# output_filter_LC.net
KiCad netlist of a schematic drawn in Altium Designer
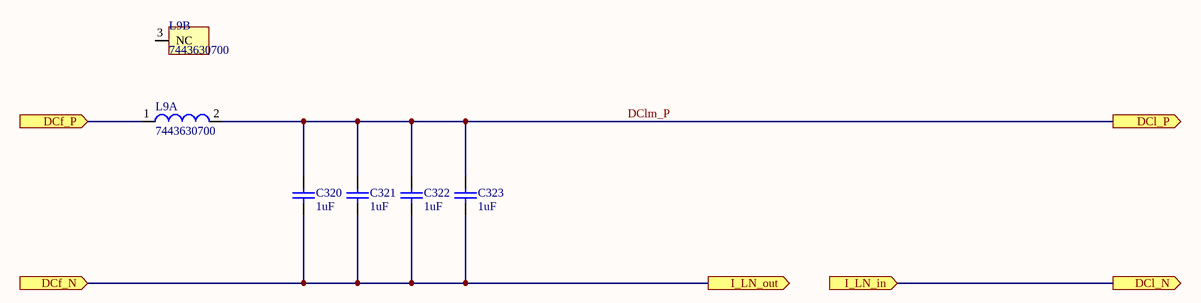
[diagram p0: output_filter_LC.SchDoc]

(export (version "E")
  (design (tool "Eeschema 10.0.6"))
  (components
    (comp (ref "C320")
      (value "1uF")
      (footprint "CAPC2225(5664)230_L")
      (description "CAP 1uF 200V ±10% 2225 (5664 Metric) Thickness 2.2mm SMD")
      (fields (field (name "TOLERANCE") "Â±10%") (field (name "Comment") "CAP 1uF 200V 2225(5664)"))
      (libsource (lib "Altium Content Vault") (part "CAP"))
    )
    (comp (ref "C321")
      (value "1uF")
      (footprint "CAPC2225(5664)230_L")
      (description "CAP 1uF 200V ±10% 2225 (5664 Metric) Thickness 2.2mm SMD")
      (fields (field (name "TOLERANCE") "Â±10%") (field (name "Comment") "CAP 1uF 200V 2225(5664)"))
      (libsource (lib "Altium Content Vault") (part "CAP"))
    )
    (comp (ref "C322")
      (value "1uF")
      (footprint "CAPC2225(5664)230_L")
      (description "CAP 1uF 200V ±10% 2225 (5664 Metric) Thickness 2.2mm SMD")
      (fields (field (name "TOLERANCE") "Â±10%") (field (name "Comment") "CAP 1uF 200V 2225(5664)"))
      (libsource (lib "Altium Content Vault") (part "CAP"))
    )
    (comp (ref "C323")
      (value "1uF")
      (footprint "CAPC2225(5664)230_L")
      (description "CAP 1uF 200V ±10% 2225 (5664 Metric) Thickness 2.2mm SMD")
      (fields (field (name "TOLERANCE") "Â±10%") (field (name "Comment") "CAP 1uF 200V 2225(5664)"))
      (libsource (lib "Altium Content Vault") (part "CAP"))
    )
    (comp (ref "L9")
      (value "7443630700")
      (footprint "WE-HCF-2013")
      (description "SMD High Current Inductor WE-HCF, L=7.00 µH")
      (libsource (lib "Altium Content Vault") (part "PAS-IND-INDUCTOR-3"))
    )
  )
  (nets
    (net (code "1") (name "/DCf_N") (class "Default")
      (node (ref "C320") (pin "1") (pinfunction "1_1") (pintype "passive"))
      (node (ref "C321") (pin "1") (pinfunction "1_1") (pintype "passive"))
      (node (ref "C322") (pin "1") (pinfunction "1_1") (pintype "passive"))
      (node (ref "C323") (pin "1") (pinfunction "1_1") (pintype "passive"))
    )
    (net (code "2") (name "/DCf_P") (class "Default")
      (node (ref "L9") (pin "1") (pinfunction "1_1") (pintype "passive"))
    )
    (net (code "4") (name "/DClm_P") (class "Default")
      (node (ref "C320") (pin "2") (pinfunction "2_2") (pintype "passive"))
      (node (ref "C321") (pin "2") (pinfunction "2_2") (pintype "passive"))
      (node (ref "C322") (pin "2") (pinfunction "2_2") (pintype "passive"))
      (node (ref "C323") (pin "2") (pinfunction "2_2") (pintype "passive"))
      (node (ref "L9") (pin "2") (pinfunction "2_2") (pintype "passive"))
    )
    (net (code "5") (name "unconnected-(L9B-NC-Pad3)") (class "Default")
      (node (ref "L9") (pin "3") (pinfunction "NC_3") (pintype "passive"))
    )
  )
)
